# lvds-omnetics_BOB.net
KiCad netlist of a schematic drawn in EAGLE
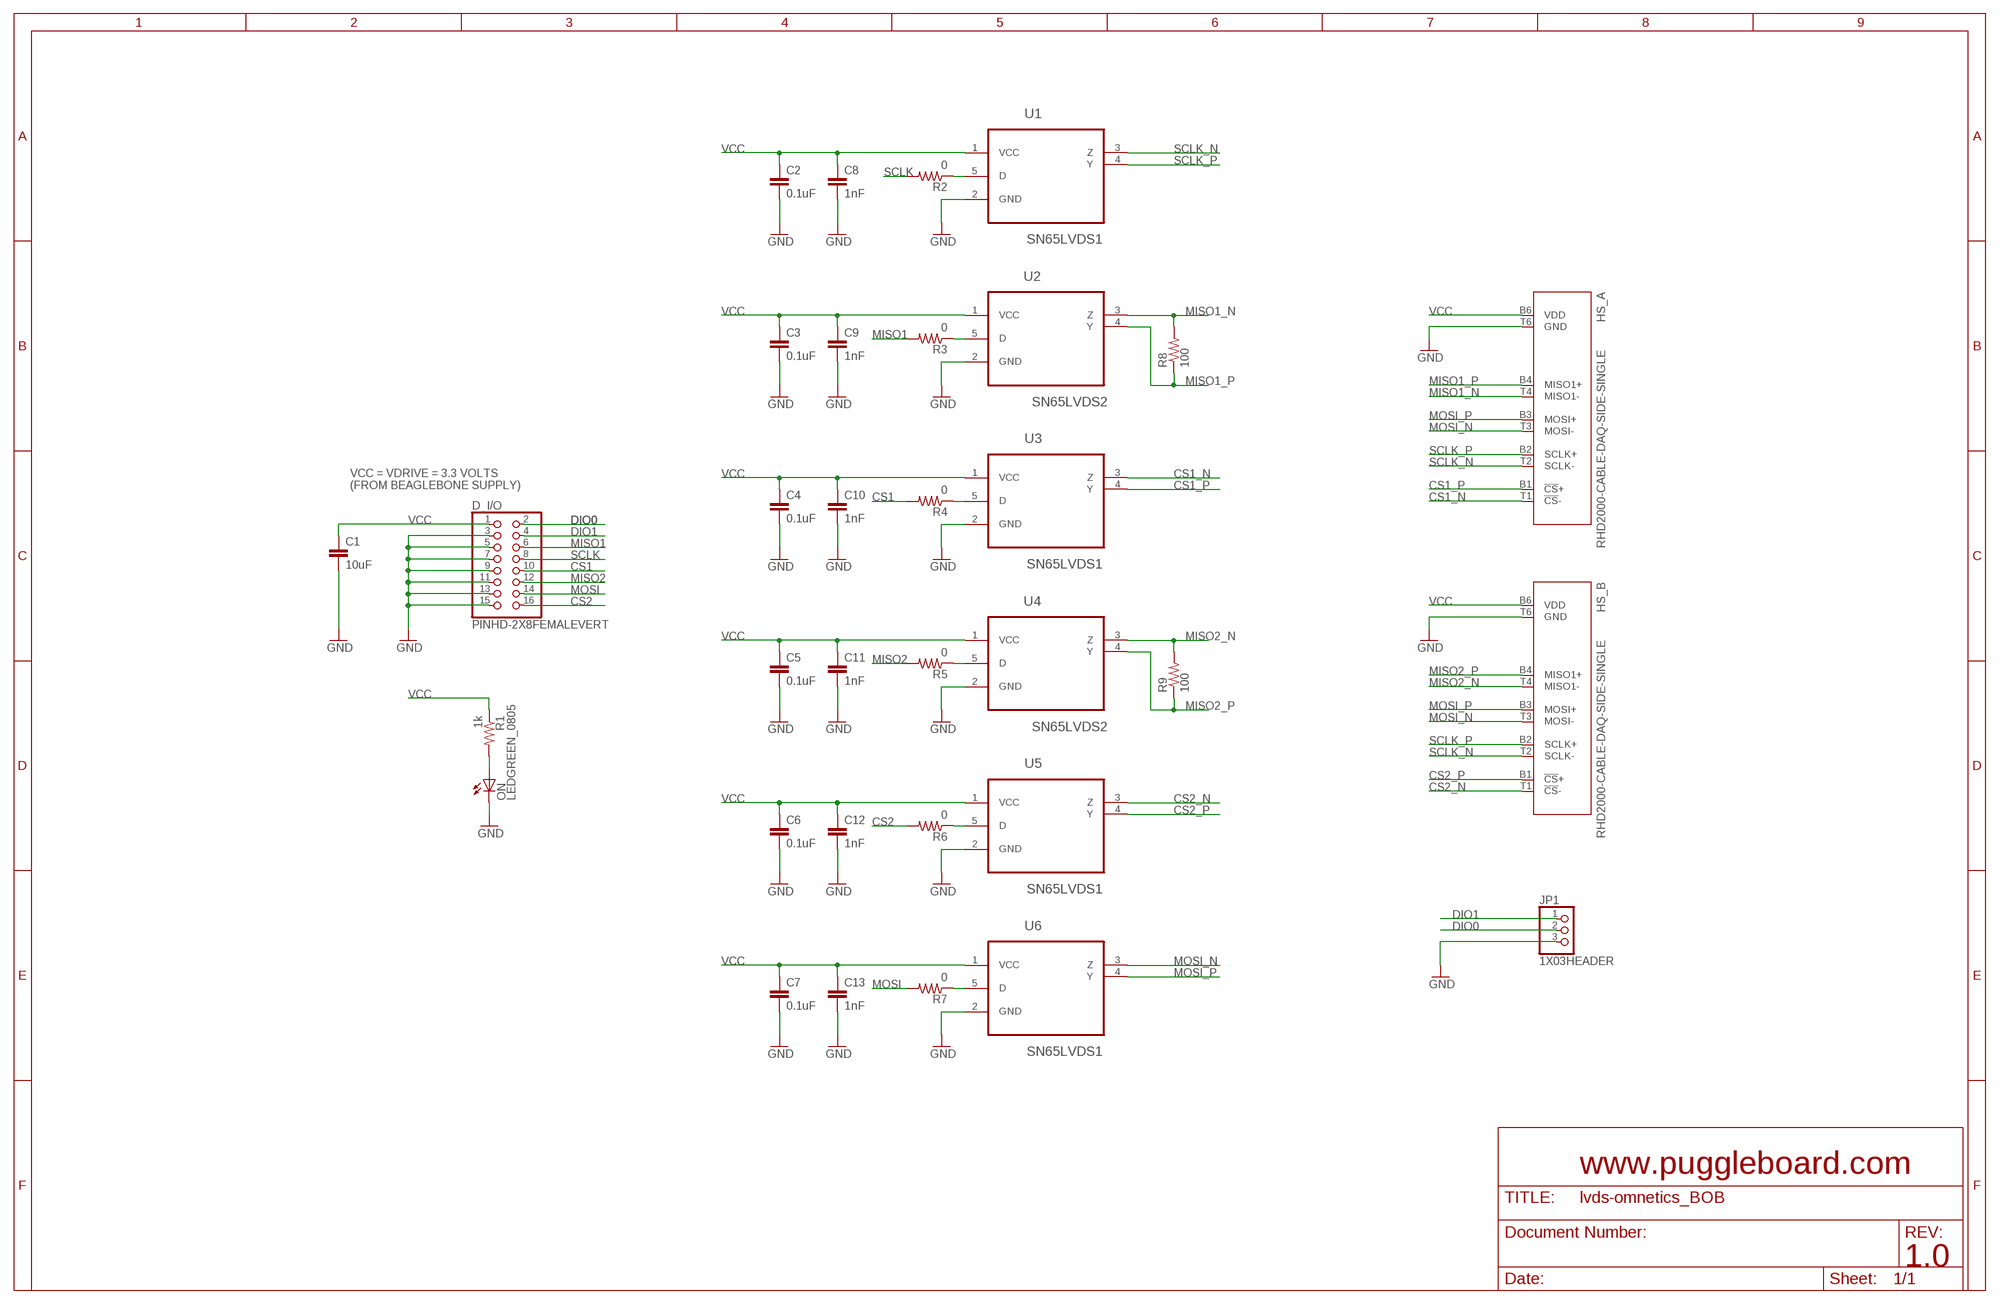
[diagram p0: schematic, sheet 1]

(export (version "E")
  (design (tool "Eeschema 10.0.6"))
  (components
    (comp (ref "C1")
      (value "10uF")
      (footprint "eagle-import:0805")
      (fields (field (name "PARTNO") "C2012X5R1Cxxxxxxx"))
      (libsource (lib "eagle-import") (part "C_0805"))
    )
    (comp (ref "C2")
      (value "0.1uF")
      (footprint "eagle-import:0603")
      (libsource (lib "eagle-import") (part "C_0603"))
    )
    (comp (ref "C3")
      (value "0.1uF")
      (footprint "eagle-import:0603")
      (libsource (lib "eagle-import") (part "C_0603"))
    )
    (comp (ref "C4")
      (value "0.1uF")
      (footprint "eagle-import:0603")
      (libsource (lib "eagle-import") (part "C_0603"))
    )
    (comp (ref "C5")
      (value "0.1uF")
      (footprint "eagle-import:0603")
      (libsource (lib "eagle-import") (part "C_0603"))
    )
    (comp (ref "C6")
      (value "0.1uF")
      (footprint "eagle-import:0603")
      (libsource (lib "eagle-import") (part "C_0603"))
    )
    (comp (ref "C7")
      (value "0.1uF")
      (footprint "eagle-import:0603")
      (libsource (lib "eagle-import") (part "C_0603"))
    )
    (comp (ref "C8")
      (value "1nF")
      (footprint "eagle-import:0603")
      (libsource (lib "eagle-import") (part "C_0603"))
    )
    (comp (ref "C9")
      (value "1nF")
      (footprint "eagle-import:0603")
      (libsource (lib "eagle-import") (part "C_0603"))
    )
    (comp (ref "C10")
      (value "1nF")
      (footprint "eagle-import:0603")
      (libsource (lib "eagle-import") (part "C_0603"))
    )
    (comp (ref "C11")
      (value "1nF")
      (footprint "eagle-import:0603")
      (libsource (lib "eagle-import") (part "C_0603"))
    )
    (comp (ref "C12")
      (value "1nF")
      (footprint "eagle-import:0603")
      (libsource (lib "eagle-import") (part "C_0603"))
    )
    (comp (ref "C13")
      (value "1nF")
      (footprint "eagle-import:0603")
      (libsource (lib "eagle-import") (part "C_0603"))
    )
    (comp (ref "D_I/O")
      (value "PINHD-2X8FEMALEVERT")
      (footprint "eagle-import:2X08")
      (fields (field (name "MPN") "PPPC082LFBN-RC"))
      (libsource (lib "eagle-import") (part "PINHD-2X8VERTFEMALE"))
    )
    (comp (ref "HS_A")
      (value "RHD2000-CABLE-DAQ-SIDE-SINGLE")
      (footprint "eagle-import:OMNETICS_PZN_12_AA-SINGLEBUS")
      (libsource (lib "eagle-import") (part "RHD2000-CABLE-DAQ-SIDE-SINGLE"))
    )
    (comp (ref "HS_B")
      (value "RHD2000-CABLE-DAQ-SIDE-SINGLE")
      (footprint "eagle-import:OMNETICS_PZN_12_AA-SINGLEBUS")
      (libsource (lib "eagle-import") (part "RHD2000-CABLE-DAQ-SIDE-SINGLE"))
    )
    (comp (ref "JP1")
      (value "1X03HEADER")
      (footprint "eagle-import:1X03")
      (fields (field (name "MPN") "961103-5604-AR"))
      (libsource (lib "eagle-import") (part "PINHD-1X3/90"))
    )
    (comp (ref "ON")
      (value "LEDGREEN_0805")
      (footprint "eagle-import:CHIP-LED0805")
      (fields (field (name "MPN") "Dialight"))
      (libsource (lib "eagle-import") (part "LED_0805GREEN"))
    )
    (comp (ref "R1")
      (value "1k")
      (footprint "eagle-import:0603")
      (fields (field (name "MPN") "ERJ-3EKFxxxxV"))
      (libsource (lib "eagle-import") (part "R_0603"))
    )
    (comp (ref "R2")
      (value "0")
      (footprint "eagle-import:0603")
      (fields (field (name "MPN") "ERJ-3EKFxxxxV"))
      (libsource (lib "eagle-import") (part "R_0603"))
    )
    (comp (ref "R3")
      (value "0")
      (footprint "eagle-import:0603")
      (fields (field (name "MPN") "ERJ-3EKFxxxxV"))
      (libsource (lib "eagle-import") (part "R_0603"))
    )
    (comp (ref "R4")
      (value "0")
      (footprint "eagle-import:0603")
      (fields (field (name "MPN") "ERJ-3EKFxxxxV"))
      (libsource (lib "eagle-import") (part "R_0603"))
    )
    (comp (ref "R5")
      (value "0")
      (footprint "eagle-import:0603")
      (fields (field (name "MPN") "ERJ-3EKFxxxxV"))
      (libsource (lib "eagle-import") (part "R_0603"))
    )
    (comp (ref "R6")
      (value "0")
      (footprint "eagle-import:0603")
      (fields (field (name "MPN") "ERJ-3EKFxxxxV"))
      (libsource (lib "eagle-import") (part "R_0603"))
    )
    (comp (ref "R7")
      (value "0")
      (footprint "eagle-import:0603")
      (fields (field (name "MPN") "ERJ-3EKFxxxxV"))
      (libsource (lib "eagle-import") (part "R_0603"))
    )
    (comp (ref "R8")
      (value "100")
      (footprint "eagle-import:0603")
      (fields (field (name "MPN") "ERJ-3EKFxxxxV"))
      (libsource (lib "eagle-import") (part "R_0603"))
    )
    (comp (ref "R9")
      (value "100")
      (footprint "eagle-import:0603")
      (fields (field (name "MPN") "ERJ-3EKFxxxxV"))
      (libsource (lib "eagle-import") (part "R_0603"))
    )
    (comp (ref "U1")
      (value "SN65LVDS1")
      (footprint "eagle-import:SOT95P280X145-5N")
      (fields (field (name "MPN") "SN65LVDS1DBVR"))
      (libsource (lib "eagle-import") (part "SN65LVDS1DBVR"))
    )
    (comp (ref "U2")
      (value "SN65LVDS2")
      (footprint "eagle-import:SOT95P280X145-5N")
      (fields (field (name "MPN") "SN65LVDS2DBVR"))
      (libsource (lib "eagle-import") (part "SN65LVDS2DBVR"))
    )
    (comp (ref "U3")
      (value "SN65LVDS1")
      (footprint "eagle-import:SOT95P280X145-5N")
      (fields (field (name "MPN") "SN65LVDS1DBVR"))
      (libsource (lib "eagle-import") (part "SN65LVDS1DBVR"))
    )
    (comp (ref "U4")
      (value "SN65LVDS2")
      (footprint "eagle-import:SOT95P280X145-5N")
      (fields (field (name "MPN") "SN65LVDS2DBVR"))
      (libsource (lib "eagle-import") (part "SN65LVDS2DBVR"))
    )
    (comp (ref "U5")
      (value "SN65LVDS1")
      (footprint "eagle-import:SOT95P280X145-5N")
      (fields (field (name "MPN") "SN65LVDS1DBVR"))
      (libsource (lib "eagle-import") (part "SN65LVDS1DBVR"))
    )
    (comp (ref "U6")
      (value "SN65LVDS1")
      (footprint "eagle-import:SOT95P280X145-5N")
      (fields (field (name "MPN") "SN65LVDS1DBVR"))
      (libsource (lib "eagle-import") (part "SN65LVDS1DBVR"))
    )
  )
  (nets
    (net (code "1") (name "/CS1") (class "Default")
      (node (ref "D_I/O") (pin "10") (pinfunction "10_10") (pintype "passive"))
      (node (ref "R4") (pin "2") (pinfunction "2_2") (pintype "passive"))
    )
    (net (code "2") (name "/CS1_N") (class "Default")
      (node (ref "HS_A") (pin "T1") (pinfunction "~{CS}-_T1") (pintype "bidirectional"))
      (node (ref "U3") (pin "3") (pinfunction "Z_3") (pintype "output"))
    )
    (net (code "3") (name "/CS1_P") (class "Default")
      (node (ref "HS_A") (pin "B1") (pinfunction "~{CS}+_B1") (pintype "bidirectional"))
      (node (ref "U3") (pin "4") (pinfunction "Y_4") (pintype "output"))
    )
    (net (code "4") (name "/CS2") (class "Default")
      (node (ref "D_I/O") (pin "16") (pinfunction "16_16") (pintype "passive"))
      (node (ref "R6") (pin "2") (pinfunction "2_2") (pintype "passive"))
    )
    (net (code "5") (name "/CS2_N") (class "Default")
      (node (ref "HS_B") (pin "T1") (pinfunction "~{CS}-_T1") (pintype "bidirectional"))
      (node (ref "U5") (pin "3") (pinfunction "Z_3") (pintype "output"))
    )
    (net (code "6") (name "/CS2_P") (class "Default")
      (node (ref "HS_B") (pin "B1") (pinfunction "~{CS}+_B1") (pintype "bidirectional"))
      (node (ref "U5") (pin "4") (pinfunction "Y_4") (pintype "output"))
    )
    (net (code "7") (name "/DIO0") (class "Default")
      (node (ref "D_I/O") (pin "2") (pinfunction "2_2") (pintype "passive"))
      (node (ref "JP1") (pin "2") (pinfunction "2_2") (pintype "passive"))
    )
    (net (code "8") (name "/DIO1") (class "Default")
      (node (ref "D_I/O") (pin "4") (pinfunction "4_4") (pintype "passive"))
      (node (ref "JP1") (pin "1") (pinfunction "1_1") (pintype "passive"))
    )
    (net (code "9") (name "/MISO1") (class "Default")
      (node (ref "D_I/O") (pin "6") (pinfunction "6_6") (pintype "passive"))
      (node (ref "R3") (pin "2") (pinfunction "2_2") (pintype "passive"))
    )
    (net (code "10") (name "/MISO1_N") (class "Default")
      (node (ref "HS_A") (pin "T4") (pinfunction "MISO1-_T4") (pintype "bidirectional"))
      (node (ref "R8") (pin "2") (pinfunction "2_2") (pintype "passive"))
      (node (ref "U2") (pin "3") (pinfunction "Z_3") (pintype "output"))
    )
    (net (code "11") (name "/MISO1_P") (class "Default")
      (node (ref "HS_A") (pin "B4") (pinfunction "MISO1+_B4") (pintype "bidirectional"))
      (node (ref "R8") (pin "1") (pinfunction "1_1") (pintype "passive"))
      (node (ref "U2") (pin "4") (pinfunction "Y_4") (pintype "output"))
    )
    (net (code "12") (name "/MISO2") (class "Default")
      (node (ref "D_I/O") (pin "12") (pinfunction "12_12") (pintype "passive"))
      (node (ref "R5") (pin "2") (pinfunction "2_2") (pintype "passive"))
    )
    (net (code "13") (name "/MISO2_N") (class "Default")
      (node (ref "HS_B") (pin "T4") (pinfunction "MISO1-_T4") (pintype "bidirectional"))
      (node (ref "R9") (pin "2") (pinfunction "2_2") (pintype "passive"))
      (node (ref "U4") (pin "3") (pinfunction "Z_3") (pintype "output"))
    )
    (net (code "14") (name "/MISO2_P") (class "Default")
      (node (ref "HS_B") (pin "B4") (pinfunction "MISO1+_B4") (pintype "bidirectional"))
      (node (ref "R9") (pin "1") (pinfunction "1_1") (pintype "passive"))
      (node (ref "U4") (pin "4") (pinfunction "Y_4") (pintype "output"))
    )
    (net (code "15") (name "/MOSI") (class "Default")
      (node (ref "D_I/O") (pin "14") (pinfunction "14_14") (pintype "passive"))
      (node (ref "R7") (pin "2") (pinfunction "2_2") (pintype "passive"))
    )
    (net (code "16") (name "/MOSI_N") (class "Default")
      (node (ref "HS_A") (pin "T3") (pinfunction "MOSI-_T3") (pintype "bidirectional"))
      (node (ref "HS_B") (pin "T3") (pinfunction "MOSI-_T3") (pintype "bidirectional"))
      (node (ref "U6") (pin "3") (pinfunction "Z_3") (pintype "output"))
    )
    (net (code "17") (name "/MOSI_P") (class "Default")
      (node (ref "HS_A") (pin "B3") (pinfunction "MOSI+_B3") (pintype "bidirectional"))
      (node (ref "HS_B") (pin "B3") (pinfunction "MOSI+_B3") (pintype "bidirectional"))
      (node (ref "U6") (pin "4") (pinfunction "Y_4") (pintype "output"))
    )
    (net (code "18") (name "/SCLK") (class "Default")
      (node (ref "D_I/O") (pin "8") (pinfunction "8_8") (pintype "passive"))
      (node (ref "R2") (pin "2") (pinfunction "2_2") (pintype "passive"))
    )
    (net (code "19") (name "/SCLK_N") (class "Default")
      (node (ref "HS_A") (pin "T2") (pinfunction "SCLK-_T2") (pintype "bidirectional"))
      (node (ref "HS_B") (pin "T2") (pinfunction "SCLK-_T2") (pintype "bidirectional"))
      (node (ref "U1") (pin "3") (pinfunction "Z_3") (pintype "output"))
    )
    (net (code "20") (name "/SCLK_P") (class "Default")
      (node (ref "HS_A") (pin "B2") (pinfunction "SCLK+_B2") (pintype "bidirectional"))
      (node (ref "HS_B") (pin "B2") (pinfunction "SCLK+_B2") (pintype "bidirectional"))
      (node (ref "U1") (pin "4") (pinfunction "Y_4") (pintype "output"))
    )
    (net (code "21") (name "/VCC") (class "Default")
      (node (ref "C1") (pin "1") (pinfunction "1_1") (pintype "passive"))
      (node (ref "C10") (pin "1") (pinfunction "1_1") (pintype "passive"))
      (node (ref "C11") (pin "1") (pinfunction "1_1") (pintype "passive"))
      (node (ref "C12") (pin "1") (pinfunction "1_1") (pintype "passive"))
      (node (ref "C13") (pin "1") (pinfunction "1_1") (pintype "passive"))
      (node (ref "C2") (pin "1") (pinfunction "1_1") (pintype "passive"))
      (node (ref "C3") (pin "1") (pinfunction "1_1") (pintype "passive"))
      (node (ref "C4") (pin "1") (pinfunction "1_1") (pintype "passive"))
      (node (ref "C5") (pin "1") (pinfunction "1_1") (pintype "passive"))
      (node (ref "C6") (pin "1") (pinfunction "1_1") (pintype "passive"))
      (node (ref "C7") (pin "1") (pinfunction "1_1") (pintype "passive"))
      (node (ref "C8") (pin "1") (pinfunction "1_1") (pintype "passive"))
      (node (ref "C9") (pin "1") (pinfunction "1_1") (pintype "passive"))
      (node (ref "D_I/O") (pin "1") (pinfunction "1_1") (pintype "passive"))
      (node (ref "HS_A") (pin "B6") (pinfunction "VDD_B6") (pintype "bidirectional"))
      (node (ref "HS_B") (pin "B6") (pinfunction "VDD_B6") (pintype "bidirectional"))
      (node (ref "R1") (pin "1") (pinfunction "1_1") (pintype "passive"))
      (node (ref "U1") (pin "1") (pinfunction "VCC_1") (pintype "power_in"))
      (node (ref "U2") (pin "1") (pinfunction "VCC_1") (pintype "power_in"))
      (node (ref "U3") (pin "1") (pinfunction "VCC_1") (pintype "power_in"))
      (node (ref "U4") (pin "1") (pinfunction "VCC_1") (pintype "power_in"))
      (node (ref "U5") (pin "1") (pinfunction "VCC_1") (pintype "power_in"))
      (node (ref "U6") (pin "1") (pinfunction "VCC_1") (pintype "power_in"))
    )
    (net (code "22") (name "GND") (class "Default")
      (node (ref "C1") (pin "2") (pinfunction "2_2") (pintype "passive"))
      (node (ref "C10") (pin "2") (pinfunction "2_2") (pintype "passive"))
      (node (ref "C11") (pin "2") (pinfunction "2_2") (pintype "passive"))
      (node (ref "C12") (pin "2") (pinfunction "2_2") (pintype "passive"))
      (node (ref "C13") (pin "2") (pinfunction "2_2") (pintype "passive"))
      (node (ref "C2") (pin "2") (pinfunction "2_2") (pintype "passive"))
      (node (ref "C3") (pin "2") (pinfunction "2_2") (pintype "passive"))
      (node (ref "C4") (pin "2") (pinfunction "2_2") (pintype "passive"))
      (node (ref "C5") (pin "2") (pinfunction "2_2") (pintype "passive"))
      (node (ref "C6") (pin "2") (pinfunction "2_2") (pintype "passive"))
      (node (ref "C7") (pin "2") (pinfunction "2_2") (pintype "passive"))
      (node (ref "C8") (pin "2") (pinfunction "2_2") (pintype "passive"))
      (node (ref "C9") (pin "2") (pinfunction "2_2") (pintype "passive"))
      (node (ref "D_I/O") (pin "11") (pinfunction "11_11") (pintype "passive"))
      (node (ref "D_I/O") (pin "13") (pinfunction "13_13") (pintype "passive"))
      (node (ref "D_I/O") (pin "15") (pinfunction "15_15") (pintype "passive"))
      (node (ref "D_I/O") (pin "3") (pinfunction "3_3") (pintype "passive"))
      (node (ref "D_I/O") (pin "5") (pinfunction "5_5") (pintype "passive"))
      (node (ref "D_I/O") (pin "7") (pinfunction "7_7") (pintype "passive"))
      (node (ref "D_I/O") (pin "9") (pinfunction "9_9") (pintype "passive"))
      (node (ref "HS_A") (pin "T6") (pinfunction "GND_T6") (pintype "power_in"))
      (node (ref "HS_B") (pin "T6") (pinfunction "GND_T6") (pintype "power_in"))
      (node (ref "JP1") (pin "3") (pinfunction "3_3") (pintype "passive"))
      (node (ref "ON") (pin "C") (pinfunction "C_C") (pintype "passive"))
      (node (ref "U1") (pin "2") (pinfunction "GND_2") (pintype "passive"))
      (node (ref "U2") (pin "2") (pinfunction "GND_2") (pintype "passive"))
      (node (ref "U3") (pin "2") (pinfunction "GND_2") (pintype "passive"))
      (node (ref "U4") (pin "2") (pinfunction "GND_2") (pintype "passive"))
      (node (ref "U5") (pin "2") (pinfunction "GND_2") (pintype "passive"))
      (node (ref "U6") (pin "2") (pinfunction "GND_2") (pintype "passive"))
    )
    (net (code "23") (name "Net-(ON-PadA)") (class "Default")
      (node (ref "ON") (pin "A") (pinfunction "A_A") (pintype "passive"))
      (node (ref "R1") (pin "2") (pinfunction "2_2") (pintype "passive"))
    )
    (net (code "24") (name "Net-(U1-D)") (class "Default")
      (node (ref "R2") (pin "1") (pinfunction "1_1") (pintype "passive"))
      (node (ref "U1") (pin "5") (pinfunction "D_5") (pintype "input"))
    )
    (net (code "25") (name "Net-(U2-D)") (class "Default")
      (node (ref "R3") (pin "1") (pinfunction "1_1") (pintype "passive"))
      (node (ref "U2") (pin "5") (pinfunction "D_5") (pintype "input"))
    )
    (net (code "26") (name "Net-(U3-D)") (class "Default")
      (node (ref "R4") (pin "1") (pinfunction "1_1") (pintype "passive"))
      (node (ref "U3") (pin "5") (pinfunction "D_5") (pintype "input"))
    )
    (net (code "27") (name "Net-(U4-D)") (class "Default")
      (node (ref "R5") (pin "1") (pinfunction "1_1") (pintype "passive"))
      (node (ref "U4") (pin "5") (pinfunction "D_5") (pintype "input"))
    )
    (net (code "28") (name "Net-(U5-D)") (class "Default")
      (node (ref "R6") (pin "1") (pinfunction "1_1") (pintype "passive"))
      (node (ref "U5") (pin "5") (pinfunction "D_5") (pintype "input"))
    )
    (net (code "29") (name "Net-(U6-D)") (class "Default")
      (node (ref "R7") (pin "1") (pinfunction "1_1") (pintype "passive"))
      (node (ref "U6") (pin "5") (pinfunction "D_5") (pintype "input"))
    )
  )
)
